# GC2USB.net
KiCad netlist of a schematic drawn in Altium Designer
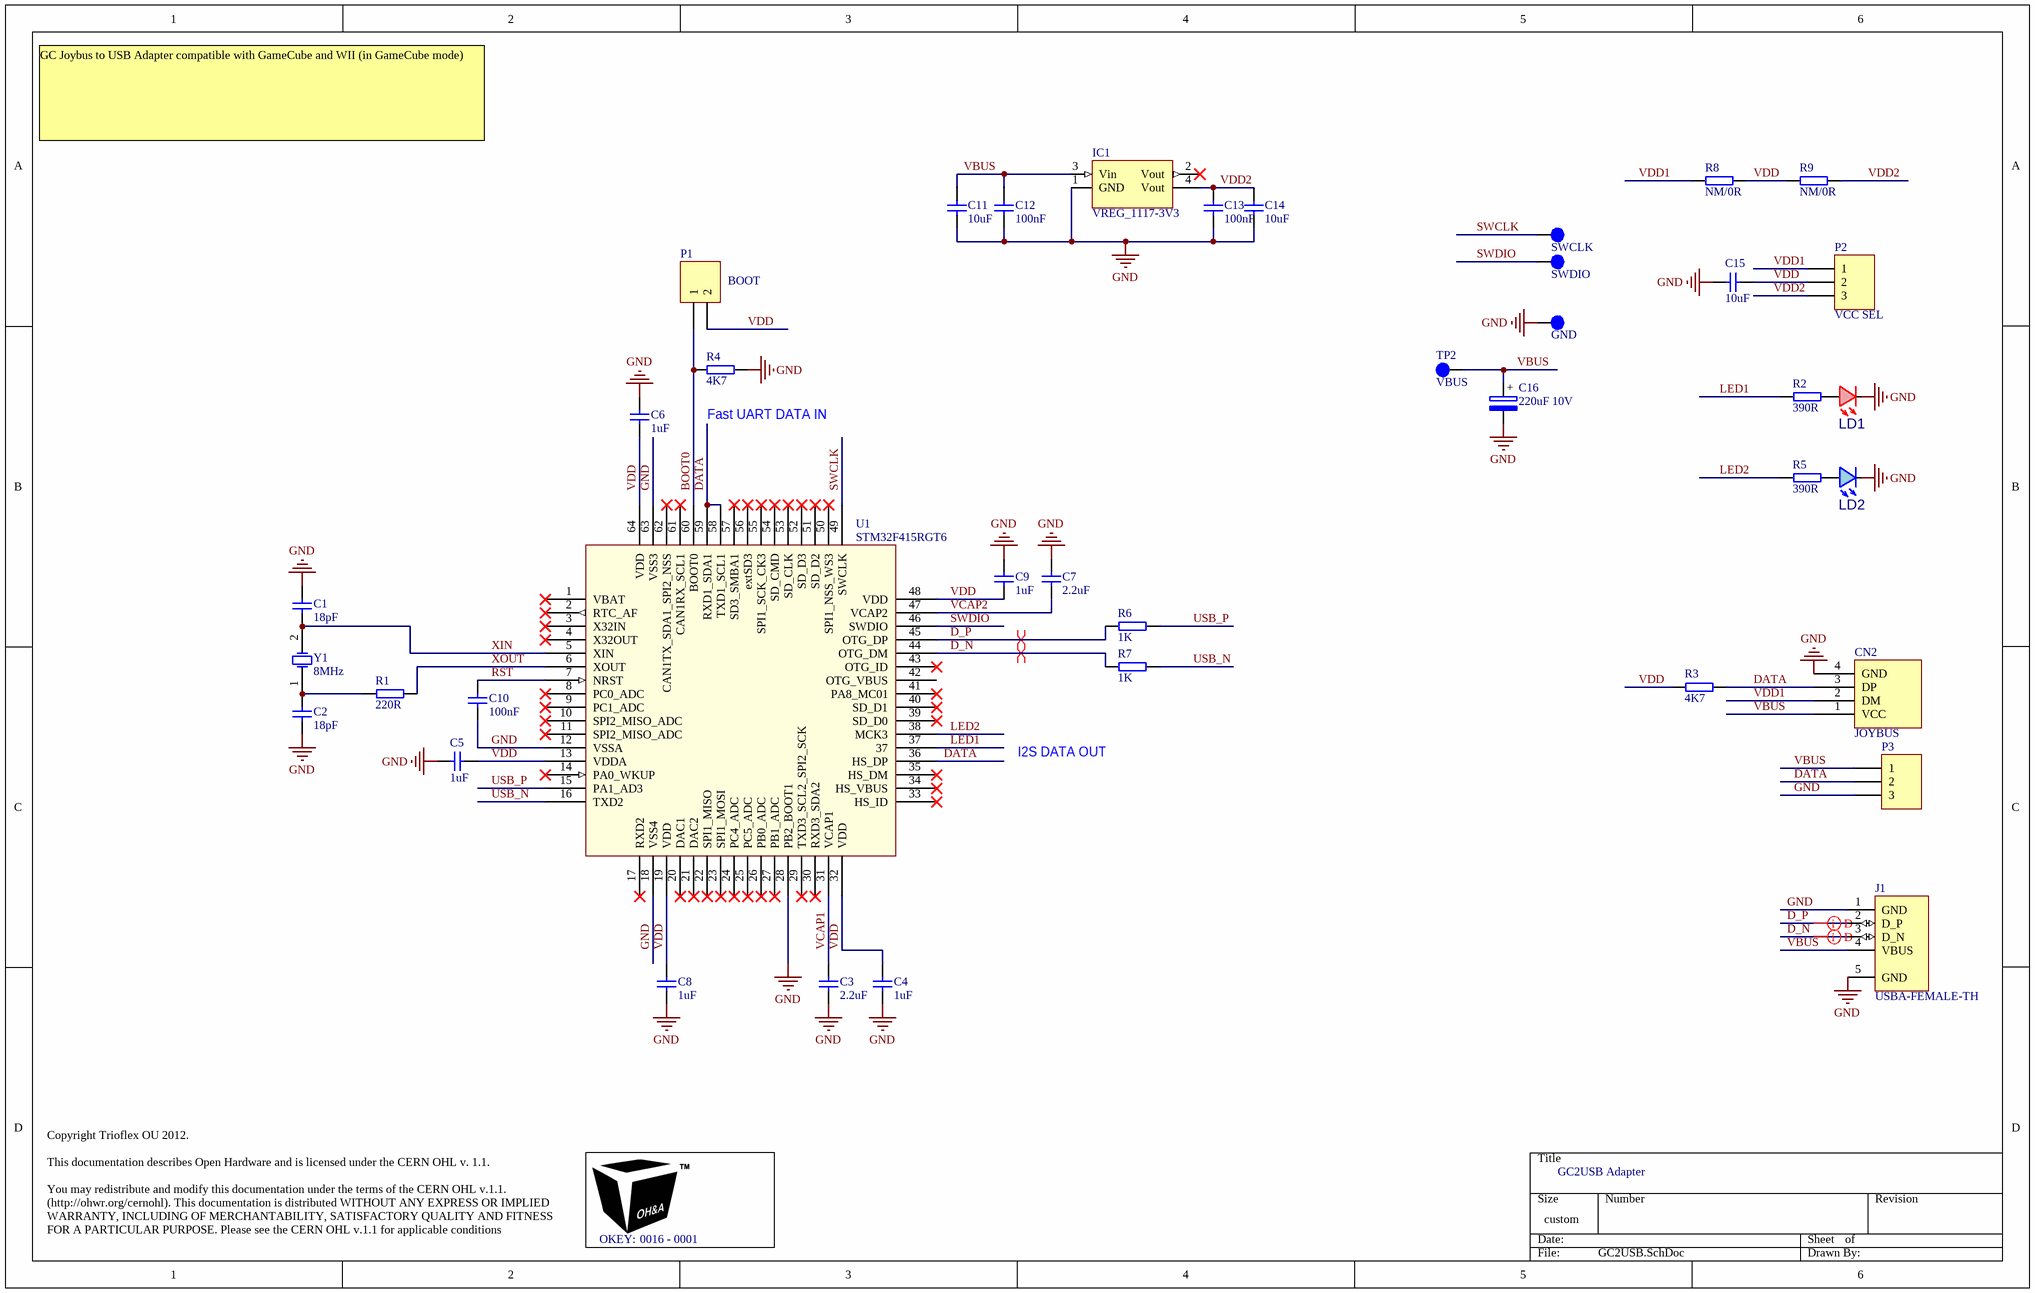
[diagram p0: GC2USB.SchDoc]

(export (version "E")
  (design (tool "Eeschema 10.0.6"))
  (components
    (comp (ref "C1")
      (value "18pF")
      (footprint "C0603")
      (description "capacitor")
      (fields (field (name "Comment") "CAP-NP"))
      (libsource (lib "trioflex-cadlib") (part "CAP-NP"))
    )
    (comp (ref "C2")
      (value "18pF")
      (footprint "C0603")
      (description "capacitor")
      (fields (field (name "Comment") "CAP-NP"))
      (libsource (lib "trioflex-cadlib") (part "CAP-NP"))
    )
    (comp (ref "C3")
      (value "2.2uF")
      (footprint "C0603")
      (description "capacitor")
      (fields (field (name "Comment") "CAP-NP"))
      (libsource (lib "trioflex-cadlib") (part "CAP-NP"))
    )
    (comp (ref "C4")
      (value "1uF")
      (footprint "C0603")
      (description "capacitor")
      (fields (field (name "Comment") "CAP-NP"))
      (libsource (lib "trioflex-cadlib") (part "CAP-NP"))
    )
    (comp (ref "C5")
      (value "1uF")
      (footprint "C0603")
      (description "capacitor")
      (fields (field (name "Comment") "CAP-NP"))
      (libsource (lib "trioflex-cadlib") (part "CAP-NP"))
    )
    (comp (ref "C6")
      (value "1uF")
      (footprint "C0603")
      (description "capacitor")
      (fields (field (name "Comment") "CAP-NP"))
      (libsource (lib "trioflex-cadlib") (part "CAP-NP"))
    )
    (comp (ref "C7")
      (value "2.2uF")
      (footprint "C0603")
      (description "capacitor")
      (fields (field (name "Comment") "CAP-NP"))
      (libsource (lib "trioflex-cadlib") (part "CAP-NP"))
    )
    (comp (ref "C8")
      (value "1uF")
      (footprint "C0603")
      (description "capacitor")
      (fields (field (name "Comment") "CAP-NP"))
      (libsource (lib "trioflex-cadlib") (part "CAP-NP"))
    )
    (comp (ref "C9")
      (value "1uF")
      (footprint "C0603")
      (description "capacitor")
      (fields (field (name "Comment") "CAP-NP"))
      (libsource (lib "trioflex-cadlib") (part "CAP-NP"))
    )
    (comp (ref "C10")
      (value "100nF")
      (footprint "C0603")
      (description "capacitor")
      (fields (field (name "Comment") "CAP-NP"))
      (libsource (lib "trioflex-cadlib") (part "CAP-NP"))
    )
    (comp (ref "C11")
      (value "10uF")
      (footprint "C0805")
      (description "capacitor")
      (fields (field (name "Comment") "CAP-NP"))
      (libsource (lib "trioflex-cadlib") (part "CAP-NP"))
    )
    (comp (ref "C12")
      (value "100nF")
      (footprint "C0603")
      (description "capacitor")
      (fields (field (name "Comment") "CAP-NP"))
      (libsource (lib "trioflex-cadlib") (part "CAP-NP"))
    )
    (comp (ref "C13")
      (value "100nF")
      (footprint "C0603")
      (description "capacitor")
      (fields (field (name "Comment") "CAP-NP"))
      (libsource (lib "trioflex-cadlib") (part "CAP-NP"))
    )
    (comp (ref "C14")
      (value "10uF")
      (footprint "C0805")
      (description "capacitor")
      (fields (field (name "Comment") "CAP-NP"))
      (libsource (lib "trioflex-cadlib") (part "CAP-NP"))
    )
    (comp (ref "C15")
      (value "10uF")
      (footprint "C0805")
      (description "capacitor")
      (fields (field (name "Comment") "CAP-NP"))
      (libsource (lib "trioflex-cadlib") (part "CAP-NP"))
    )
    (comp (ref "C16")
      (value "220uF 10V")
      (footprint "D-7MM")
      (description "polarized capacitor")
      (libsource (lib "trioflex-cadlib") (part "CAP-P"))
    )
    (comp (ref "CN2")
      (value "JOYBUS")
      (footprint "4pin-header-2mm")
      (description "USB_PCBCON")
      (libsource (lib "xilant") (part "USB_PCBCON"))
    )
    (comp (ref "GND")
      (value "TP")
      (footprint "TP-SMD-2mm")
      (description "Testpoint")
      (libsource (lib "trioflex-cadlib") (part "TP"))
    )
    (comp (ref "IC1")
      (value "VREG_1117-3V3")
      (footprint "SOT223")
      (description "VREG_1117")
      (libsource (lib "trioflex-cadlib") (part "VREG_1117"))
    )
    (comp (ref "J1")
      (value "USBA-FEMALE-TH")
      (footprint "USBA-FEMALE-THR-HOLE")
      (description "USBA-FEMALE-THR-HOLE")
      (libsource (lib "trioflex") (part "USBA-FEMALE-THR-HOLE"))
    )
    (comp (ref "LD1")
      (value "RED-LED")
      (footprint "0603")
      (libsource (lib "trioflex-cadlib") (part "RED-LED"))
    )
    (comp (ref "LD2")
      (value "BLUE-LED")
      (footprint "0603")
      (libsource (lib "trioflex-cadlib") (part "BLUE-LED"))
    )
    (comp (ref "P1")
      (value "BOOT")
      (footprint "HDR1X2")
      (description "Header, 2-Pin")
      (fields (field (name "PUBLISHER") "Altium Limited"))
      (libsource (lib "Miscellaneous Connectors") (part "Header 2"))
    )
    (comp (ref "P2")
      (value "VCC SEL")
      (footprint "HDR1X3")
      (description "Header, 3-Pin")
      (fields (field (name "PUBLISHER") "Altium Limited"))
      (libsource (lib "Miscellaneous Connectors") (part "Header 3"))
    )
    (comp (ref "P3")
      (value "*")
      (footprint "HDR1X3")
      (description "Header, 3-Pin")
      (fields (field (name "PUBLISHER") "Altium Limited"))
      (libsource (lib "Miscellaneous Connectors") (part "Header 3"))
    )
    (comp (ref "R1")
      (value "220R")
      (footprint "R0603")
      (description "Resistor")
      (fields (field (name "Comment") "RES"))
      (libsource (lib "trioflex-cadlib") (part "RES"))
    )
    (comp (ref "R2")
      (value "390R")
      (footprint "R0603")
      (description "Resistor")
      (fields (field (name "Comment") "RES"))
      (libsource (lib "trioflex-cadlib") (part "RES"))
    )
    (comp (ref "R3")
      (value "4K7")
      (footprint "R0603")
      (description "Resistor")
      (fields (field (name "Comment") "RES"))
      (libsource (lib "trioflex-cadlib") (part "RES"))
    )
    (comp (ref "R4")
      (value "4K7")
      (footprint "R0603")
      (description "Resistor")
      (fields (field (name "Comment") "RES"))
      (libsource (lib "trioflex-cadlib") (part "RES"))
    )
    (comp (ref "R5")
      (value "390R")
      (footprint "R0603")
      (description "Resistor")
      (fields (field (name "Comment") "RES"))
      (libsource (lib "trioflex-cadlib") (part "RES"))
    )
    (comp (ref "R6")
      (value "1K")
      (footprint "R0603")
      (description "Resistor")
      (libsource (lib "trioflex-cadlib") (part "RES"))
    )
    (comp (ref "R7")
      (value "1K")
      (footprint "R0603")
      (description "Resistor")
      (libsource (lib "trioflex-cadlib") (part "RES"))
    )
    (comp (ref "R8")
      (value "NM/0R")
      (footprint "R0603")
      (description "Resistor")
      (libsource (lib "trioflex-cadlib") (part "RES"))
    )
    (comp (ref "R9")
      (value "NM/0R")
      (footprint "R0603")
      (description "Resistor")
      (libsource (lib "trioflex-cadlib") (part "RES"))
    )
    (comp (ref "SWCLK")
      (value "TP")
      (footprint "TP-SMD-2mm")
      (description "Testpoint")
      (libsource (lib "trioflex-cadlib") (part "TP"))
    )
    (comp (ref "SWDIO")
      (value "TP")
      (footprint "TP-SMD-2mm")
      (description "Testpoint")
      (libsource (lib "trioflex-cadlib") (part "TP"))
    )
    (comp (ref "TP2")
      (value "VBUS")
      (footprint "TP-SMD-2mm")
      (description "Testpoint")
      (libsource (lib "trioflex-cadlib") (part "TP"))
    )
    (comp (ref "U1")
      (value "STM32F415RGT6")
      (footprint "STM-TQFP64")
      (libsource (lib "trioflex-cadlib") (part "STM32F415RGT6"))
    )
    (comp (ref "Y1")
      (value "8MHz")
      (footprint "HC49-THSMD")
      (description "Crystal Oscillator")
      (fields (field (name "Comment") "XTAL-2P"))
      (libsource (lib "trioflex-cadlib") (part "XTAL-2P"))
    )
  )
  (nets
    (net (code "1") (name "/BOOT0") (class "Default")
      (node (ref "P1") (pin "1") (pinfunction "1_1") (pintype "passive"))
      (node (ref "R4") (pin "1") (pinfunction "1_1") (pintype "passive"))
      (node (ref "U1") (pin "60") (pinfunction "BOOT0_60") (pintype "passive"))
    )
    (net (code "2") (name "/DATA") (class "Default")
      (node (ref "CN2") (pin "3") (pinfunction "DP_3") (pintype "passive"))
      (node (ref "P3") (pin "2") (pinfunction "2_2") (pintype "passive"))
      (node (ref "R3") (pin "1") (pinfunction "1_1") (pintype "passive"))
      (node (ref "U1") (pin "36") (pinfunction "HS_DP_36") (pintype "passive"))
      (node (ref "U1") (pin "58") (pinfunction "TXD1_SCL1_58") (pintype "passive"))
      (node (ref "U1") (pin "59") (pinfunction "RXD1_SDA1_59") (pintype "passive"))
    )
    (net (code "3") (name "/D_N") (class "Default")
      (node (ref "J1") (pin "3") (pinfunction "D_N_3") (pintype "bidirectional"))
      (node (ref "R7") (pin "1") (pinfunction "1_1") (pintype "passive"))
      (node (ref "U1") (pin "44") (pinfunction "OTG_DM_44") (pintype "passive"))
    )
    (net (code "4") (name "/D_P") (class "Default")
      (node (ref "J1") (pin "2") (pinfunction "D_P_2") (pintype "bidirectional"))
      (node (ref "R6") (pin "1") (pinfunction "1_1") (pintype "passive"))
      (node (ref "U1") (pin "45") (pinfunction "OTG_DP_45") (pintype "passive"))
    )
    (net (code "5") (name "/LED1") (class "Default")
      (node (ref "R2") (pin "2") (pinfunction "2_2") (pintype "passive"))
      (node (ref "U1") (pin "37") (pinfunction "37_37") (pintype "passive"))
    )
    (net (code "6") (name "/LED2") (class "Default")
      (node (ref "R5") (pin "2") (pinfunction "2_2") (pintype "passive"))
      (node (ref "U1") (pin "38") (pinfunction "MCK3_38") (pintype "passive"))
    )
    (net (code "7") (name "/RST") (class "Default")
      (node (ref "C10") (pin "1") (pinfunction "1_1") (pintype "passive"))
      (node (ref "U1") (pin "7") (pinfunction "NRST_7") (pintype "input"))
    )
    (net (code "8") (name "/SWCLK") (class "Default")
      (node (ref "SWCLK") (pin "1") (pinfunction "1_1") (pintype "passive"))
      (node (ref "U1") (pin "49") (pinfunction "SWCLK_49") (pintype "passive"))
    )
    (net (code "9") (name "/SWDIO") (class "Default")
      (node (ref "SWDIO") (pin "1") (pinfunction "1_1") (pintype "passive"))
      (node (ref "U1") (pin "46") (pinfunction "SWDIO_46") (pintype "passive"))
    )
    (net (code "10") (name "/USB_N") (class "Default")
      (node (ref "R7") (pin "2") (pinfunction "2_2") (pintype "passive"))
      (node (ref "U1") (pin "16") (pinfunction "TXD2_16") (pintype "passive"))
    )
    (net (code "11") (name "/USB_P") (class "Default")
      (node (ref "R6") (pin "2") (pinfunction "2_2") (pintype "passive"))
      (node (ref "U1") (pin "15") (pinfunction "PA1_AD3_15") (pintype "passive"))
    )
    (net (code "12") (name "/VBUS") (class "Default")
      (node (ref "C11") (pin "1") (pinfunction "1_1") (pintype "passive"))
      (node (ref "C12") (pin "1") (pinfunction "1_1") (pintype "passive"))
      (node (ref "C16") (pin "1") (pinfunction "1_1") (pintype "passive"))
      (node (ref "CN2") (pin "1") (pinfunction "VCC_1") (pintype "power_in"))
      (node (ref "IC1") (pin "3") (pinfunction "Vin_3") (pintype "input"))
      (node (ref "J1") (pin "4") (pinfunction "VBUS_4") (pintype "power_in"))
      (node (ref "P3") (pin "1") (pinfunction "1_1") (pintype "passive"))
      (node (ref "TP2") (pin "1") (pinfunction "1_1") (pintype "passive"))
    )
    (net (code "13") (name "/VCAP1") (class "Default")
      (node (ref "C3") (pin "1") (pinfunction "1_1") (pintype "passive"))
      (node (ref "U1") (pin "31") (pinfunction "VCAP1_31") (pintype "passive"))
    )
    (net (code "14") (name "/VCAP2") (class "Default")
      (node (ref "C7") (pin "1") (pinfunction "1_1") (pintype "passive"))
      (node (ref "U1") (pin "47") (pinfunction "VCAP2_47") (pintype "passive"))
    )
    (net (code "15") (name "/VDD") (class "Default")
      (node (ref "C15") (pin "2") (pinfunction "2_2") (pintype "passive"))
      (node (ref "C4") (pin "2") (pinfunction "2_2") (pintype "passive"))
      (node (ref "C5") (pin "1") (pinfunction "1_1") (pintype "passive"))
      (node (ref "C6") (pin "2") (pinfunction "2_2") (pintype "passive"))
      (node (ref "C8") (pin "1") (pinfunction "1_1") (pintype "passive"))
      (node (ref "C9") (pin "2") (pinfunction "2_2") (pintype "passive"))
      (node (ref "P1") (pin "2") (pinfunction "2_2") (pintype "passive"))
      (node (ref "P2") (pin "2") (pinfunction "2_2") (pintype "passive"))
      (node (ref "R3") (pin "2") (pinfunction "2_2") (pintype "passive"))
      (node (ref "R8") (pin "2") (pinfunction "2_2") (pintype "passive"))
      (node (ref "R9") (pin "1") (pinfunction "1_1") (pintype "passive"))
      (node (ref "U1") (pin "13") (pinfunction "VDDA_13") (pintype "passive"))
      (node (ref "U1") (pin "19") (pinfunction "VDD_19") (pintype "passive"))
      (node (ref "U1") (pin "32") (pinfunction "VDD_32") (pintype "passive"))
      (node (ref "U1") (pin "48") (pinfunction "VDD_48") (pintype "passive"))
      (node (ref "U1") (pin "64") (pinfunction "VDD_64") (pintype "passive"))
    )
    (net (code "16") (name "/VDD1") (class "Default")
      (node (ref "CN2") (pin "2") (pinfunction "DM_2") (pintype "passive"))
      (node (ref "P2") (pin "1") (pinfunction "1_1") (pintype "passive"))
      (node (ref "R8") (pin "1") (pinfunction "1_1") (pintype "passive"))
    )
    (net (code "17") (name "/VDD2") (class "Default")
      (node (ref "C13") (pin "1") (pinfunction "1_1") (pintype "passive"))
      (node (ref "C14") (pin "1") (pinfunction "1_1") (pintype "passive"))
      (node (ref "IC1") (pin "4") (pinfunction "Vout_4") (pintype "passive"))
      (node (ref "P2") (pin "3") (pinfunction "3_3") (pintype "passive"))
      (node (ref "R9") (pin "2") (pinfunction "2_2") (pintype "passive"))
    )
    (net (code "18") (name "/XIN") (class "Default")
      (node (ref "C1") (pin "2") (pinfunction "2_2") (pintype "passive"))
      (node (ref "U1") (pin "5") (pinfunction "XIN_5") (pintype "passive"))
      (node (ref "Y1") (pin "2") (pinfunction "2_2") (pintype "passive"))
    )
    (net (code "19") (name "/XOUT") (class "Default")
      (node (ref "R1") (pin "2") (pinfunction "2_2") (pintype "passive"))
      (node (ref "U1") (pin "6") (pinfunction "XOUT_6") (pintype "passive"))
    )
    (net (code "20") (name "GND") (class "Default")
      (node (ref "C1") (pin "1") (pinfunction "1_1") (pintype "passive"))
      (node (ref "C10") (pin "2") (pinfunction "2_2") (pintype "passive"))
      (node (ref "C11") (pin "2") (pinfunction "2_2") (pintype "passive"))
      (node (ref "C12") (pin "2") (pinfunction "2_2") (pintype "passive"))
      (node (ref "C13") (pin "2") (pinfunction "2_2") (pintype "passive"))
      (node (ref "C14") (pin "2") (pinfunction "2_2") (pintype "passive"))
      (node (ref "C15") (pin "1") (pinfunction "1_1") (pintype "passive"))
      (node (ref "C16") (pin "2") (pinfunction "2_2") (pintype "passive"))
      (node (ref "C2") (pin "2") (pinfunction "2_2") (pintype "passive"))
      (node (ref "C3") (pin "2") (pinfunction "2_2") (pintype "passive"))
      (node (ref "C4") (pin "1") (pinfunction "1_1") (pintype "passive"))
      (node (ref "C5") (pin "2") (pinfunction "2_2") (pintype "passive"))
      (node (ref "C6") (pin "1") (pinfunction "1_1") (pintype "passive"))
      (node (ref "C7") (pin "2") (pinfunction "2_2") (pintype "passive"))
      (node (ref "C8") (pin "2") (pinfunction "2_2") (pintype "passive"))
      (node (ref "C9") (pin "1") (pinfunction "1_1") (pintype "passive"))
      (node (ref "CN2") (pin "4") (pinfunction "GND_4") (pintype "power_in"))
      (node (ref "GND") (pin "1") (pinfunction "1_1") (pintype "passive"))
      (node (ref "IC1") (pin "1") (pinfunction "GND_1") (pintype "passive"))
      (node (ref "J1") (pin "1") (pinfunction "GND_1") (pintype "power_in"))
      (node (ref "J1") (pin "5") (pinfunction "GND_5") (pintype "passive"))
      (node (ref "LD1") (pin "C") (pinfunction "C-_C") (pintype "passive"))
      (node (ref "LD2") (pin "C") (pinfunction "C-_C") (pintype "passive"))
      (node (ref "P3") (pin "3") (pinfunction "3_3") (pintype "passive"))
      (node (ref "R4") (pin "2") (pinfunction "2_2") (pintype "passive"))
      (node (ref "U1") (pin "12") (pinfunction "VSSA_12") (pintype "passive"))
      (node (ref "U1") (pin "18") (pinfunction "VSS4_18") (pintype "passive"))
      (node (ref "U1") (pin "28") (pinfunction "PB2_BOOT1_28") (pintype "passive"))
      (node (ref "U1") (pin "63") (pinfunction "VSS3_63") (pintype "passive"))
    )
    (net (code "21") (name "Net-(LD1-A+)") (class "Default")
      (node (ref "LD1") (pin "A") (pinfunction "A+_A") (pintype "passive"))
      (node (ref "R2") (pin "1") (pinfunction "1_1") (pintype "passive"))
    )
    (net (code "22") (name "Net-(LD2-A+)") (class "Default")
      (node (ref "LD2") (pin "A") (pinfunction "A+_A") (pintype "passive"))
      (node (ref "R5") (pin "1") (pinfunction "1_1") (pintype "passive"))
    )
    (net (code "23") (name "Net-(Y1-OSC1)") (class "Default")
      (node (ref "C2") (pin "1") (pinfunction "1_1") (pintype "passive"))
      (node (ref "R1") (pin "1") (pinfunction "1_1") (pintype "passive"))
      (node (ref "Y1") (pin "1") (pinfunction "OSC1_1") (pintype "passive"))
    )
    (net (code "24") (name "unconnected-(IC1-Vout-Pad2)") (class "Default")
      (node (ref "IC1") (pin "2") (pinfunction "Vout_2") (pintype "output+no_connect"))
    )
    (net (code "25") (name "unconnected-(U1-CAN1RX_SCL1-Pad61)") (class "Default")
      (node (ref "U1") (pin "61") (pinfunction "CAN1RX_SCL1_61") (pintype "passive+no_connect"))
    )
    (net (code "26") (name "unconnected-(U1-CAN1TX_SDA1_SPI2_NSS-Pad62)") (class "Default")
      (node (ref "U1") (pin "62") (pinfunction "CAN1TX_SDA1_SPI2_NSS_62") (pintype "passive+no_connect"))
    )
    (net (code "27") (name "unconnected-(U1-DAC1-Pad20)") (class "Default")
      (node (ref "U1") (pin "20") (pinfunction "DAC1_20") (pintype "passive+no_connect"))
    )
    (net (code "28") (name "unconnected-(U1-DAC2-Pad21)") (class "Default")
      (node (ref "U1") (pin "21") (pinfunction "DAC2_21") (pintype "passive+no_connect"))
    )
    (net (code "29") (name "unconnected-(U1-HS_DM-Pad35)") (class "Default")
      (node (ref "U1") (pin "35") (pinfunction "HS_DM_35") (pintype "passive+no_connect"))
    )
    (net (code "30") (name "unconnected-(U1-HS_ID-Pad33)") (class "Default")
      (node (ref "U1") (pin "33") (pinfunction "HS_ID_33") (pintype "passive+no_connect"))
    )
    (net (code "31") (name "unconnected-(U1-HS_VBUS-Pad34)") (class "Default")
      (node (ref "U1") (pin "34") (pinfunction "HS_VBUS_34") (pintype "passive+no_connect"))
    )
    (net (code "32") (name "unconnected-(U1-OTG_ID-Pad43)") (class "Default")
      (node (ref "U1") (pin "43") (pinfunction "OTG_ID_43") (pintype "passive+no_connect"))
    )
    (net (code "33") (name "unconnected-(U1-OTG_VBUS-Pad42)") (class "Default")
      (node (ref "U1") (pin "42") (pinfunction "OTG_VBUS_42") (pintype "passive"))
    )
    (net (code "34") (name "unconnected-(U1-PA0_WKUP-Pad14)") (class "Default")
      (node (ref "U1") (pin "14") (pinfunction "PA0_WKUP_14") (pintype "input+no_connect"))
    )
    (net (code "35") (name "unconnected-(U1-PA8_MC01-Pad41)") (class "Default")
      (node (ref "U1") (pin "41") (pinfunction "PA8_MC01_41") (pintype "passive+no_connect"))
    )
    (net (code "36") (name "unconnected-(U1-PB0_ADC-Pad26)") (class "Default")
      (node (ref "U1") (pin "26") (pinfunction "PB0_ADC_26") (pintype "passive+no_connect"))
    )
    (net (code "37") (name "unconnected-(U1-PB1_ADC-Pad27)") (class "Default")
      (node (ref "U1") (pin "27") (pinfunction "PB1_ADC_27") (pintype "passive+no_connect"))
    )
    (net (code "38") (name "unconnected-(U1-PC0_ADC-Pad8)") (class "Default")
      (node (ref "U1") (pin "8") (pinfunction "PC0_ADC_8") (pintype "passive+no_connect"))
    )
    (net (code "39") (name "unconnected-(U1-PC1_ADC-Pad9)") (class "Default")
      (node (ref "U1") (pin "9") (pinfunction "PC1_ADC_9") (pintype "passive+no_connect"))
    )
    (net (code "40") (name "unconnected-(U1-PC4_ADC-Pad24)") (class "Default")
      (node (ref "U1") (pin "24") (pinfunction "PC4_ADC_24") (pintype "passive+no_connect"))
    )
    (net (code "41") (name "unconnected-(U1-PC5_ADC-Pad25)") (class "Default")
      (node (ref "U1") (pin "25") (pinfunction "PC5_ADC_25") (pintype "passive+no_connect"))
    )
    (net (code "42") (name "unconnected-(U1-RTC_AF-Pad2)") (class "Default")
      (node (ref "U1") (pin "2") (pinfunction "RTC_AF_2") (pintype "output+no_connect"))
    )
    (net (code "43") (name "unconnected-(U1-RXD2-Pad17)") (class "Default")
      (node (ref "U1") (pin "17") (pinfunction "RXD2_17") (pintype "passive+no_connect"))
    )
    (net (code "44") (name "unconnected-(U1-RXD3_SDA2-Pad30)") (class "Default")
      (node (ref "U1") (pin "30") (pinfunction "RXD3_SDA2_30") (pintype "passive+no_connect"))
    )
    (net (code "45") (name "unconnected-(U1-SD3_SMBA1-Pad57)") (class "Default")
      (node (ref "U1") (pin "57") (pinfunction "SD3_SMBA1_57") (pintype "passive+no_connect"))
    )
    (net (code "46") (name "unconnected-(U1-SD_CLK-Pad53)") (class "Default")
      (node (ref "U1") (pin "53") (pinfunction "SD_CLK_53") (pintype "passive+no_connect"))
    )
    (net (code "47") (name "unconnected-(U1-SD_CMD-Pad54)") (class "Default")
      (node (ref "U1") (pin "54") (pinfunction "SD_CMD_54") (pintype "passive+no_connect"))
    )
    (net (code "48") (name "unconnected-(U1-SD_D0-Pad39)") (class "Default")
      (node (ref "U1") (pin "39") (pinfunction "SD_D0_39") (pintype "passive+no_connect"))
    )
    (net (code "49") (name "unconnected-(U1-SD_D1-Pad40)") (class "Default")
      (node (ref "U1") (pin "40") (pinfunction "SD_D1_40") (pintype "passive+no_connect"))
    )
    (net (code "50") (name "unconnected-(U1-SD_D2-Pad51)") (class "Default")
      (node (ref "U1") (pin "51") (pinfunction "SD_D2_51") (pintype "passive+no_connect"))
    )
    (net (code "51") (name "unconnected-(U1-SD_D3-Pad52)") (class "Default")
      (node (ref "U1") (pin "52") (pinfunction "SD_D3_52") (pintype "passive+no_connect"))
    )
    (net (code "52") (name "unconnected-(U1-SPI1_MISO-Pad22)") (class "Default")
      (node (ref "U1") (pin "22") (pinfunction "SPI1_MISO_22") (pintype "passive+no_connect"))
    )
    (net (code "53") (name "unconnected-(U1-SPI1_MOSI-Pad23)") (class "Default")
      (node (ref "U1") (pin "23") (pinfunction "SPI1_MOSI_23") (pintype "passive+no_connect"))
    )
    (net (code "54") (name "unconnected-(U1-SPI1_NSS_WS3-Pad50)") (class "Default")
      (node (ref "U1") (pin "50") (pinfunction "SPI1_NSS_WS3_50") (pintype "passive+no_connect"))
    )
    (net (code "55") (name "unconnected-(U1-SPI1_SCK_CK3-Pad55)") (class "Default")
      (node (ref "U1") (pin "55") (pinfunction "SPI1_SCK_CK3_55") (pintype "passive+no_connect"))
    )
    (net (code "56") (name "unconnected-(U1-SPI2_MISO_ADC-Pad10)") (class "Default")
      (node (ref "U1") (pin "10") (pinfunction "SPI2_MISO_ADC_10") (pintype "passive+no_connect"))
    )
    (net (code "57") (name "unconnected-(U1-SPI2_MISO_ADC-Pad11)") (class "Default")
      (node (ref "U1") (pin "11") (pinfunction "SPI2_MISO_ADC_11") (pintype "passive+no_connect"))
    )
    (net (code "58") (name "unconnected-(U1-TXD3_SCL2_SPI2_SCK-Pad29)") (class "Default")
      (node (ref "U1") (pin "29") (pinfunction "TXD3_SCL2_SPI2_SCK_29") (pintype "passive+no_connect"))
    )
    (net (code "59") (name "unconnected-(U1-VBAT-Pad1)") (class "Default")
      (node (ref "U1") (pin "1") (pinfunction "VBAT_1") (pintype "passive+no_connect"))
    )
    (net (code "60") (name "unconnected-(U1-X32IN-Pad3)") (class "Default")
      (node (ref "U1") (pin "3") (pinfunction "X32IN_3") (pintype "passive+no_connect"))
    )
    (net (code "61") (name "unconnected-(U1-X32OUT-Pad4)") (class "Default")
      (node (ref "U1") (pin "4") (pinfunction "X32OUT_4") (pintype "passive+no_connect"))
    )
    (net (code "62") (name "unconnected-(U1-extSD3-Pad56)") (class "Default")
      (node (ref "U1") (pin "56") (pinfunction "extSD3_56") (pintype "passive+no_connect"))
    )
  )
)
